# STM32_10FSR.net
KiCad netlist of a schematic drawn in EAGLE
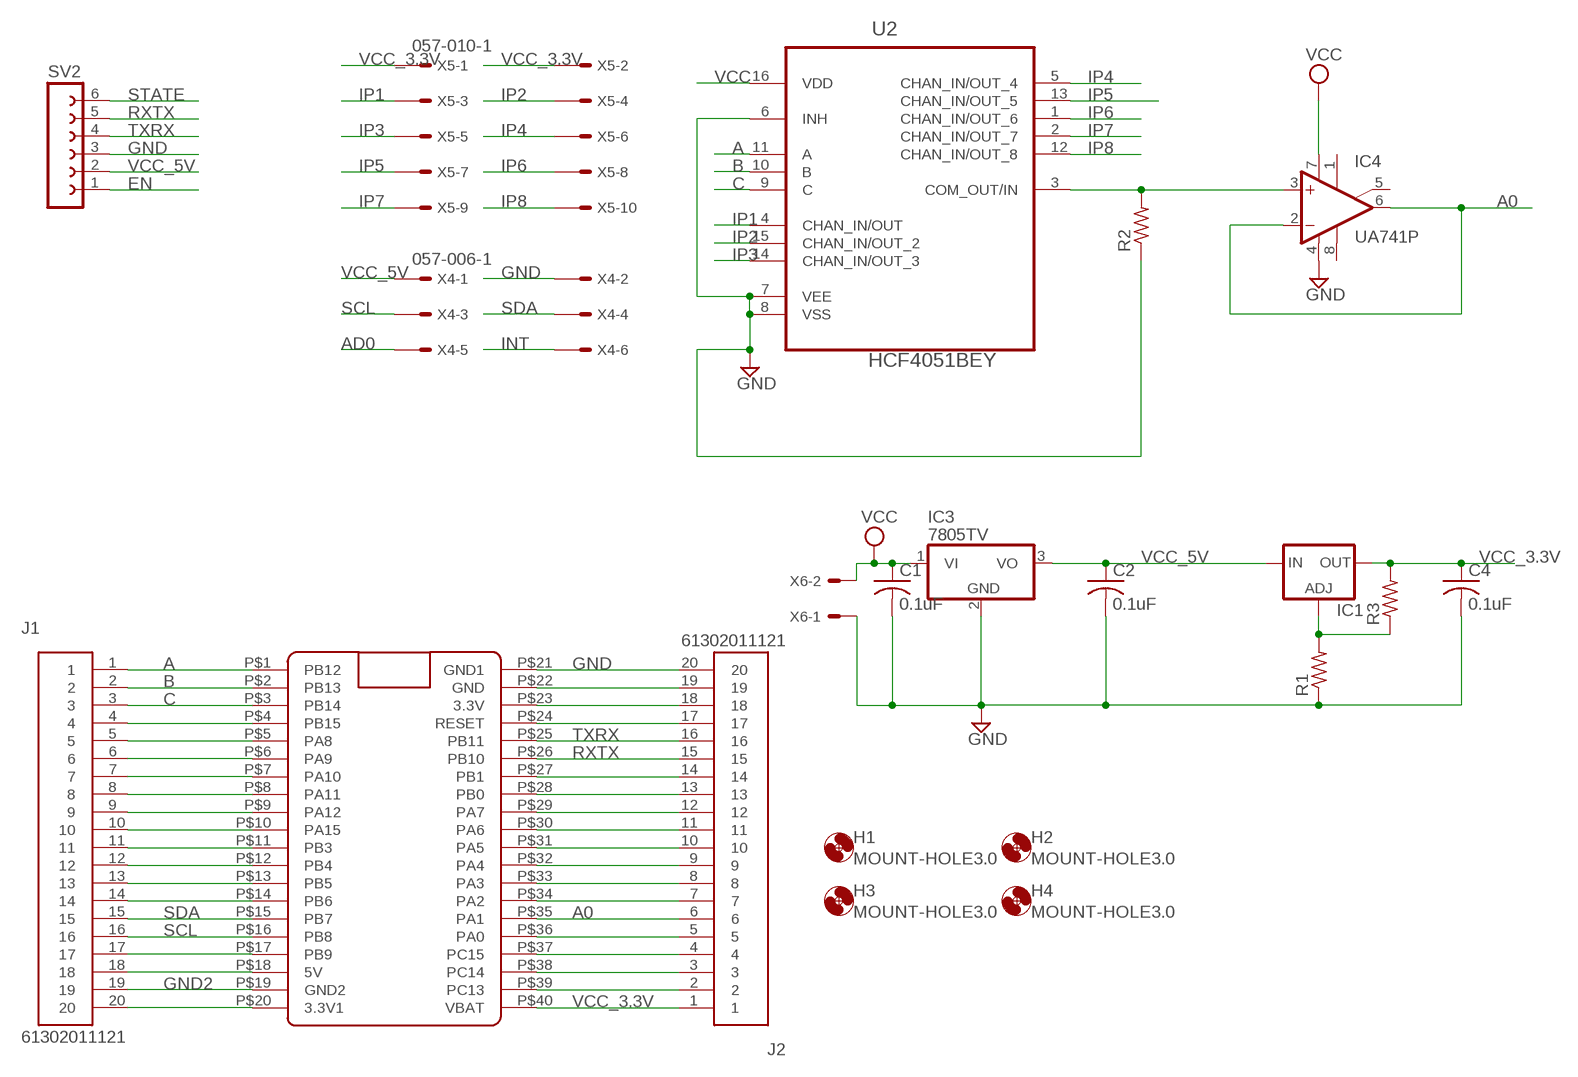
[diagram p0: schematic, sheet 1]

(export (version "E")
  (design (tool "Eeschema 10.0.6"))
  (components
    (comp (ref "C1")
      (value "0.1uF")
      (footprint "eagle-import:C025-024X044")
      (libsource (lib "eagle-import") (part "C-US025-024X044"))
    )
    (comp (ref "C2")
      (value "0.1uF")
      (footprint "eagle-import:C025-024X044")
      (libsource (lib "eagle-import") (part "C-US025-024X044"))
    )
    (comp (ref "C4")
      (value "0.1uF")
      (footprint "eagle-import:C025-024X044")
      (libsource (lib "eagle-import") (part "C-US025-024X044"))
    )
    (comp (ref "H1")
      (value "MOUNT-HOLE3.0")
      (footprint "eagle-import:3,0")
      (libsource (lib "eagle-import") (part "MOUNT-HOLE3.0"))
    )
    (comp (ref "H2")
      (value "MOUNT-HOLE3.0")
      (footprint "eagle-import:3,0")
      (libsource (lib "eagle-import") (part "MOUNT-HOLE3.0"))
    )
    (comp (ref "H3")
      (value "MOUNT-HOLE3.0")
      (footprint "eagle-import:3,0")
      (libsource (lib "eagle-import") (part "MOUNT-HOLE3.0"))
    )
    (comp (ref "H4")
      (value "MOUNT-HOLE3.0")
      (footprint "eagle-import:3,0")
      (libsource (lib "eagle-import") (part "MOUNT-HOLE3.0"))
    )
    (comp (ref "IC1")
      (value "LM317TS")
      (footprint "eagle-import:317TS")
      (libsource (lib "eagle-import") (part "LM317TS"))
    )
    (comp (ref "IC3")
      (value "7805TV")
      (footprint "eagle-import:TO220V")
      (libsource (lib "eagle-import") (part "78TV05"))
    )
    (comp (ref "IC4")
      (value "UA741P")
      (footprint "eagle-import:DIL08")
      (libsource (lib "eagle-import") (part "741PUA"))
    )
    (comp (ref "J1")
      (value "61302011121")
      (footprint "eagle-import:61302011121")
      (fields
        (field (name "DIGIKEY_PART_NUMBER") "732-5329-ND")
        (field (name "MANUFACTURER") "Wurth Electronics Inc.")
        (field (name "CREATED_BY") "PCBLayout.com")
      )
      (libsource (lib "eagle-import") (part "61302011121"))
    )
    (comp (ref "J2")
      (value "61302011121")
      (footprint "eagle-import:61302011121")
      (fields
        (field (name "DIGIKEY_PART_NUMBER") "732-5329-ND")
        (field (name "MANUFACTURER") "Wurth Electronics Inc.")
        (field (name "CREATED_BY") "PCBLayout.com")
      )
      (libsource (lib "eagle-import") (part "61302011121"))
    )
    (comp (ref "R1")
      (value "R-US_0204/7")
      (footprint "eagle-import:0204_7")
      (libsource (lib "eagle-import") (part "R-US_0204/7"))
    )
    (comp (ref "R2")
      (value "R-US_0204/7")
      (footprint "eagle-import:0204_7")
      (libsource (lib "eagle-import") (part "R-US_0204/7"))
    )
    (comp (ref "R3")
      (value "R-US_0204/7")
      (footprint "eagle-import:0204_7")
      (libsource (lib "eagle-import") (part "R-US_0204/7"))
    )
    (comp (ref "SV2")
      (value "FE06-1")
      (footprint "eagle-import:FE06")
      (libsource (lib "eagle-import") (part "FE06-1"))
    )
    (comp (ref "U$1")
      (value "BLUE_PILLADVANCED")
      (footprint "eagle-import:BLUE_PILL_ADV")
      (libsource (lib "eagle-import") (part "BLUE_PILLADVANCED"))
    )
    (comp (ref "U2")
      (value "HCF4051BEY")
      (footprint "eagle-import:DIP254P762X510-16")
      (fields (field (name "MF") "STMicroelectronics"))
      (libsource (lib "eagle-import") (part "HCF4051BEY"))
    )
    (comp (ref "X4")
      (value "057-006-1")
      (footprint "eagle-import:057-006-1")
      (libsource (lib "eagle-import") (part "057-006-1"))
    )
    (comp (ref "X5")
      (value "057-010-1")
      (footprint "eagle-import:057-010-1")
      (libsource (lib "eagle-import") (part "057-010-1"))
    )
    (comp (ref "X6")
      (value "KK-156-2")
      (footprint "eagle-import:KK-156-2")
      (fields (field (name "MF") "MOLEX"))
      (libsource (lib "eagle-import") (part "KK-156-2"))
    )
  )
  (nets
    (net (code "1") (name "/A") (class "Default")
      (node (ref "J1") (pin "1") (pinfunction "1_1") (pintype "passive"))
      (node (ref "U$1") (pin "P$1") (pinfunction "PB12_P$1") (pintype "bidirectional"))
      (node (ref "U2") (pin "11") (pinfunction "A_11") (pintype "input"))
    )
    (net (code "2") (name "/A0") (class "Default")
      (node (ref "IC4") (pin "2") (pinfunction "-IN_2") (pintype "input"))
      (node (ref "IC4") (pin "6") (pinfunction "OUT_6") (pintype "output"))
      (node (ref "J2") (pin "6") (pinfunction "6_6") (pintype "passive"))
      (node (ref "U$1") (pin "P$35") (pinfunction "PA1_P$35") (pintype "bidirectional"))
    )
    (net (code "3") (name "/AD0") (class "Default")
      (node (ref "X4") (pin "5") (pinfunction "S_5") (pintype "passive"))
    )
    (net (code "4") (name "/B") (class "Default")
      (node (ref "J1") (pin "2") (pinfunction "2_2") (pintype "passive"))
      (node (ref "U$1") (pin "P$2") (pinfunction "PB13_P$2") (pintype "bidirectional"))
      (node (ref "U2") (pin "10") (pinfunction "B_10") (pintype "input"))
    )
    (net (code "5") (name "/C") (class "Default")
      (node (ref "J1") (pin "3") (pinfunction "3_3") (pintype "passive"))
      (node (ref "U$1") (pin "P$3") (pinfunction "PB14_P$3") (pintype "bidirectional"))
      (node (ref "U2") (pin "9") (pinfunction "C_9") (pintype "input"))
    )
    (net (code "6") (name "/EN") (class "Default")
      (node (ref "SV2") (pin "1") (pinfunction "1_1") (pintype "passive"))
    )
    (net (code "7") (name "/GND2") (class "Default")
      (node (ref "J1") (pin "19") (pinfunction "19_19") (pintype "passive"))
      (node (ref "U$1") (pin "P$19") (pinfunction "GND2_P$19") (pintype "bidirectional"))
    )
    (net (code "8") (name "/INT") (class "Default")
      (node (ref "X4") (pin "6") (pinfunction "S_6") (pintype "passive"))
    )
    (net (code "9") (name "/IP1") (class "Default")
      (node (ref "U2") (pin "4") (pinfunction "CHAN_IN/OUT_4") (pintype "bidirectional"))
      (node (ref "X5") (pin "3") (pinfunction "S_3") (pintype "passive"))
    )
    (net (code "10") (name "/IP2") (class "Default")
      (node (ref "U2") (pin "15") (pinfunction "CHAN_IN/OUT_2_15") (pintype "bidirectional"))
      (node (ref "X5") (pin "4") (pinfunction "S_4") (pintype "passive"))
    )
    (net (code "11") (name "/IP3") (class "Default")
      (node (ref "U2") (pin "14") (pinfunction "CHAN_IN/OUT_3_14") (pintype "bidirectional"))
      (node (ref "X5") (pin "5") (pinfunction "S_5") (pintype "passive"))
    )
    (net (code "12") (name "/IP4") (class "Default")
      (node (ref "U2") (pin "5") (pinfunction "CHAN_IN/OUT_4_5") (pintype "bidirectional"))
      (node (ref "X5") (pin "6") (pinfunction "S_6") (pintype "passive"))
    )
    (net (code "13") (name "/IP5") (class "Default")
      (node (ref "U2") (pin "13") (pinfunction "CHAN_IN/OUT_5_13") (pintype "bidirectional"))
      (node (ref "X5") (pin "7") (pinfunction "S_7") (pintype "passive"))
    )
    (net (code "14") (name "/IP6") (class "Default")
      (node (ref "U2") (pin "1") (pinfunction "CHAN_IN/OUT_6_1") (pintype "bidirectional"))
      (node (ref "X5") (pin "8") (pinfunction "S_8") (pintype "passive"))
    )
    (net (code "15") (name "/IP7") (class "Default")
      (node (ref "U2") (pin "2") (pinfunction "CHAN_IN/OUT_7_2") (pintype "bidirectional"))
      (node (ref "X5") (pin "9") (pinfunction "S_9") (pintype "passive"))
    )
    (net (code "16") (name "/IP8") (class "Default")
      (node (ref "U2") (pin "12") (pinfunction "CHAN_IN/OUT_8_12") (pintype "bidirectional"))
      (node (ref "X5") (pin "10") (pinfunction "S_10") (pintype "passive"))
    )
    (net (code "17") (name "/RXTX") (class "Default")
      (node (ref "J2") (pin "15") (pinfunction "15_15") (pintype "passive"))
      (node (ref "SV2") (pin "5") (pinfunction "5_5") (pintype "passive"))
      (node (ref "U$1") (pin "P$26") (pinfunction "PB10_P$26") (pintype "bidirectional"))
    )
    (net (code "18") (name "/SCL") (class "Default")
      (node (ref "J1") (pin "16") (pinfunction "16_16") (pintype "passive"))
      (node (ref "U$1") (pin "P$16") (pinfunction "PB8_P$16") (pintype "bidirectional"))
      (node (ref "X4") (pin "3") (pinfunction "S_3") (pintype "passive"))
    )
    (net (code "19") (name "/SDA") (class "Default")
      (node (ref "J1") (pin "15") (pinfunction "15_15") (pintype "passive"))
      (node (ref "U$1") (pin "P$15") (pinfunction "PB7_P$15") (pintype "bidirectional"))
      (node (ref "X4") (pin "4") (pinfunction "S_4") (pintype "passive"))
    )
    (net (code "20") (name "/STATE") (class "Default")
      (node (ref "SV2") (pin "6") (pinfunction "6_6") (pintype "passive"))
    )
    (net (code "21") (name "/TXRX") (class "Default")
      (node (ref "J2") (pin "16") (pinfunction "16_16") (pintype "passive"))
      (node (ref "SV2") (pin "4") (pinfunction "4_4") (pintype "passive"))
      (node (ref "U$1") (pin "P$25") (pinfunction "PB11_P$25") (pintype "bidirectional"))
    )
    (net (code "22") (name "/VCC_3.3V") (class "Default")
      (node (ref "C4") (pin "1") (pinfunction "1_1") (pintype "passive"))
      (node (ref "IC1") (pin "2") (pinfunction "OUT_2") (pintype "passive"))
      (node (ref "J2") (pin "1") (pinfunction "1_1") (pintype "passive"))
      (node (ref "R3") (pin "2") (pinfunction "2_2") (pintype "passive"))
      (node (ref "U$1") (pin "P$40") (pinfunction "VBAT_P$40") (pintype "bidirectional"))
      (node (ref "X5") (pin "1") (pinfunction "S_1") (pintype "passive"))
      (node (ref "X5") (pin "2") (pinfunction "S_2") (pintype "passive"))
    )
    (net (code "23") (name "/VCC_5V") (class "Default")
      (node (ref "C2") (pin "1") (pinfunction "1_1") (pintype "passive"))
      (node (ref "IC1") (pin "3") (pinfunction "IN_3") (pintype "input"))
      (node (ref "IC3") (pin "3") (pinfunction "VO_3") (pintype "passive"))
      (node (ref "SV2") (pin "2") (pinfunction "2_2") (pintype "passive"))
      (node (ref "X4") (pin "1") (pinfunction "S_1") (pintype "passive"))
    )
    (net (code "24") (name "GND") (class "Default")
      (node (ref "C1") (pin "2") (pinfunction "2_2") (pintype "passive"))
      (node (ref "C2") (pin "2") (pinfunction "2_2") (pintype "passive"))
      (node (ref "C4") (pin "2") (pinfunction "2_2") (pintype "passive"))
      (node (ref "IC3") (pin "2") (pinfunction "GND_2") (pintype "passive"))
      (node (ref "IC4") (pin "4") (pinfunction "V-_4") (pintype "power_in"))
      (node (ref "J2") (pin "20") (pinfunction "20_20") (pintype "passive"))
      (node (ref "R1") (pin "1") (pinfunction "1_1") (pintype "passive"))
      (node (ref "R2") (pin "1") (pinfunction "1_1") (pintype "passive"))
      (node (ref "SV2") (pin "3") (pinfunction "3_3") (pintype "passive"))
      (node (ref "U$1") (pin "P$21") (pinfunction "GND1_P$21") (pintype "power_in"))
      (node (ref "U2") (pin "6") (pinfunction "INH_6") (pintype "passive"))
      (node (ref "U2") (pin "7") (pinfunction "VEE_7") (pintype "power_in"))
      (node (ref "U2") (pin "8") (pinfunction "VSS_8") (pintype "power_in"))
      (node (ref "X4") (pin "2") (pinfunction "S_2") (pintype "passive"))
      (node (ref "X6") (pin "1") (pinfunction "S_1") (pintype "passive"))
    )
    (net (code "25") (name "Net-(IC1-ADJ)") (class "Default")
      (node (ref "IC1") (pin "1") (pinfunction "ADJ_1") (pintype "input"))
      (node (ref "R1") (pin "2") (pinfunction "2_2") (pintype "passive"))
      (node (ref "R3") (pin "1") (pinfunction "1_1") (pintype "passive"))
    )
    (net (code "26") (name "Net-(IC4-+IN)") (class "Default")
      (node (ref "IC4") (pin "3") (pinfunction "+IN_3") (pintype "input"))
      (node (ref "R2") (pin "2") (pinfunction "2_2") (pintype "passive"))
      (node (ref "U2") (pin "3") (pinfunction "COM_OUT/IN_3") (pintype "bidirectional"))
    )
    (net (code "27") (name "Net-(U$1-3.3V)") (class "Default")
      (node (ref "J2") (pin "18") (pinfunction "18_18") (pintype "passive"))
      (node (ref "U$1") (pin "P$23") (pinfunction "3.3V_P$23") (pintype "bidirectional"))
    )
    (net (code "28") (name "Net-(U$1-3.3V1)") (class "Default")
      (node (ref "J1") (pin "20") (pinfunction "20_20") (pintype "passive"))
      (node (ref "U$1") (pin "P$20") (pinfunction "3.3V1_P$20") (pintype "bidirectional"))
    )
    (net (code "29") (name "Net-(U$1-5V)") (class "Default")
      (node (ref "J1") (pin "18") (pinfunction "18_18") (pintype "passive"))
      (node (ref "U$1") (pin "P$18") (pinfunction "5V_P$18") (pintype "bidirectional"))
    )
    (net (code "30") (name "Net-(U$1-GND)") (class "Default")
      (node (ref "J2") (pin "19") (pinfunction "19_19") (pintype "passive"))
      (node (ref "U$1") (pin "P$22") (pinfunction "GND_P$22") (pintype "bidirectional"))
    )
    (net (code "31") (name "Net-(U$1-PA0)") (class "Default")
      (node (ref "J2") (pin "5") (pinfunction "5_5") (pintype "passive"))
      (node (ref "U$1") (pin "P$36") (pinfunction "PA0_P$36") (pintype "bidirectional"))
    )
    (net (code "32") (name "Net-(U$1-PA2)") (class "Default")
      (node (ref "J2") (pin "7") (pinfunction "7_7") (pintype "passive"))
      (node (ref "U$1") (pin "P$34") (pinfunction "PA2_P$34") (pintype "bidirectional"))
    )
    (net (code "33") (name "Net-(U$1-PA3)") (class "Default")
      (node (ref "J2") (pin "8") (pinfunction "8_8") (pintype "passive"))
      (node (ref "U$1") (pin "P$33") (pinfunction "PA3_P$33") (pintype "bidirectional"))
    )
    (net (code "34") (name "Net-(U$1-PA4)") (class "Default")
      (node (ref "J2") (pin "9") (pinfunction "9_9") (pintype "passive"))
      (node (ref "U$1") (pin "P$32") (pinfunction "PA4_P$32") (pintype "bidirectional"))
    )
    (net (code "35") (name "Net-(U$1-PA5)") (class "Default")
      (node (ref "J2") (pin "10") (pinfunction "10_10") (pintype "passive"))
      (node (ref "U$1") (pin "P$31") (pinfunction "PA5_P$31") (pintype "bidirectional"))
    )
    (net (code "36") (name "Net-(U$1-PA6)") (class "Default")
      (node (ref "J2") (pin "11") (pinfunction "11_11") (pintype "passive"))
      (node (ref "U$1") (pin "P$30") (pinfunction "PA6_P$30") (pintype "bidirectional"))
    )
    (net (code "37") (name "Net-(U$1-PA7)") (class "Default")
      (node (ref "J2") (pin "12") (pinfunction "12_12") (pintype "passive"))
      (node (ref "U$1") (pin "P$29") (pinfunction "PA7_P$29") (pintype "bidirectional"))
    )
    (net (code "38") (name "Net-(U$1-PA8)") (class "Default")
      (node (ref "J1") (pin "5") (pinfunction "5_5") (pintype "passive"))
      (node (ref "U$1") (pin "P$5") (pinfunction "PA8_P$5") (pintype "bidirectional"))
    )
    (net (code "39") (name "Net-(U$1-PA9)") (class "Default")
      (node (ref "J1") (pin "6") (pinfunction "6_6") (pintype "passive"))
      (node (ref "U$1") (pin "P$6") (pinfunction "PA9_P$6") (pintype "bidirectional"))
    )
    (net (code "40") (name "Net-(U$1-PA10)") (class "Default")
      (node (ref "J1") (pin "7") (pinfunction "7_7") (pintype "passive"))
      (node (ref "U$1") (pin "P$7") (pinfunction "PA10_P$7") (pintype "bidirectional"))
    )
    (net (code "41") (name "Net-(U$1-PA11)") (class "Default")
      (node (ref "J1") (pin "8") (pinfunction "8_8") (pintype "passive"))
      (node (ref "U$1") (pin "P$8") (pinfunction "PA11_P$8") (pintype "bidirectional"))
    )
    (net (code "42") (name "Net-(U$1-PA12)") (class "Default")
      (node (ref "J1") (pin "9") (pinfunction "9_9") (pintype "passive"))
      (node (ref "U$1") (pin "P$9") (pinfunction "PA12_P$9") (pintype "bidirectional"))
    )
    (net (code "43") (name "Net-(U$1-PA15)") (class "Default")
      (node (ref "J1") (pin "10") (pinfunction "10_10") (pintype "passive"))
      (node (ref "U$1") (pin "P$10") (pinfunction "PA15_P$10") (pintype "bidirectional"))
    )
    (net (code "44") (name "Net-(U$1-PB0)") (class "Default")
      (node (ref "J2") (pin "13") (pinfunction "13_13") (pintype "passive"))
      (node (ref "U$1") (pin "P$28") (pinfunction "PB0_P$28") (pintype "bidirectional"))
    )
    (net (code "45") (name "Net-(U$1-PB1)") (class "Default")
      (node (ref "J2") (pin "14") (pinfunction "14_14") (pintype "passive"))
      (node (ref "U$1") (pin "P$27") (pinfunction "PB1_P$27") (pintype "bidirectional"))
    )
    (net (code "46") (name "Net-(U$1-PB3)") (class "Default")
      (node (ref "J1") (pin "11") (pinfunction "11_11") (pintype "passive"))
      (node (ref "U$1") (pin "P$11") (pinfunction "PB3_P$11") (pintype "bidirectional"))
    )
    (net (code "47") (name "Net-(U$1-PB4)") (class "Default")
      (node (ref "J1") (pin "12") (pinfunction "12_12") (pintype "passive"))
      (node (ref "U$1") (pin "P$12") (pinfunction "PB4_P$12") (pintype "bidirectional"))
    )
    (net (code "48") (name "Net-(U$1-PB5)") (class "Default")
      (node (ref "J1") (pin "13") (pinfunction "13_13") (pintype "passive"))
      (node (ref "U$1") (pin "P$13") (pinfunction "PB5_P$13") (pintype "bidirectional"))
    )
    (net (code "49") (name "Net-(U$1-PB6)") (class "Default")
      (node (ref "J1") (pin "14") (pinfunction "14_14") (pintype "passive"))
      (node (ref "U$1") (pin "P$14") (pinfunction "PB6_P$14") (pintype "bidirectional"))
    )
    (net (code "50") (name "Net-(U$1-PB9)") (class "Default")
      (node (ref "J1") (pin "17") (pinfunction "17_17") (pintype "passive"))
      (node (ref "U$1") (pin "P$17") (pinfunction "PB9_P$17") (pintype "bidirectional"))
    )
    (net (code "51") (name "Net-(U$1-PB15)") (class "Default")
      (node (ref "J1") (pin "4") (pinfunction "4_4") (pintype "passive"))
      (node (ref "U$1") (pin "P$4") (pinfunction "PB15_P$4") (pintype "bidirectional"))
    )
    (net (code "52") (name "Net-(U$1-PC13)") (class "Default")
      (node (ref "J2") (pin "2") (pinfunction "2_2") (pintype "passive"))
      (node (ref "U$1") (pin "P$39") (pinfunction "PC13_P$39") (pintype "bidirectional"))
    )
    (net (code "53") (name "Net-(U$1-PC14)") (class "Default")
      (node (ref "J2") (pin "3") (pinfunction "3_3") (pintype "passive"))
      (node (ref "U$1") (pin "P$38") (pinfunction "PC14_P$38") (pintype "bidirectional"))
    )
    (net (code "54") (name "Net-(U$1-PC15)") (class "Default")
      (node (ref "J2") (pin "4") (pinfunction "4_4") (pintype "passive"))
      (node (ref "U$1") (pin "P$37") (pinfunction "PC15_P$37") (pintype "bidirectional"))
    )
    (net (code "55") (name "Net-(U$1-RESET)") (class "Default")
      (node (ref "J2") (pin "17") (pinfunction "17_17") (pintype "passive"))
      (node (ref "U$1") (pin "P$24") (pinfunction "RESET_P$24") (pintype "bidirectional"))
    )
    (net (code "56") (name "VCC") (class "Default")
      (node (ref "C1") (pin "1") (pinfunction "1_1") (pintype "passive"))
      (node (ref "IC3") (pin "1") (pinfunction "VI_1") (pintype "input"))
      (node (ref "IC4") (pin "7") (pinfunction "V+_7") (pintype "power_in"))
      (node (ref "U2") (pin "16") (pinfunction "VDD_16") (pintype "power_in"))
      (node (ref "X6") (pin "2") (pinfunction "S_2") (pintype "passive"))
    )
    (net (code "57") (name "unconnected-(IC4-ON1-Pad1)") (class "Default")
      (node (ref "IC4") (pin "1") (pinfunction "ON1_1") (pintype "passive"))
    )
    (net (code "58") (name "unconnected-(IC4-ON2-Pad5)") (class "Default")
      (node (ref "IC4") (pin "5") (pinfunction "ON2_5") (pintype "passive"))
    )
    (net (code "59") (name "unconnected-(IC4-OPT-Pad8)") (class "Default")
      (node (ref "IC4") (pin "8") (pinfunction "OPT_8") (pintype "passive"))
    )
  )
)
